# main.net
KiCad netlist of a schematic drawn in EAGLE
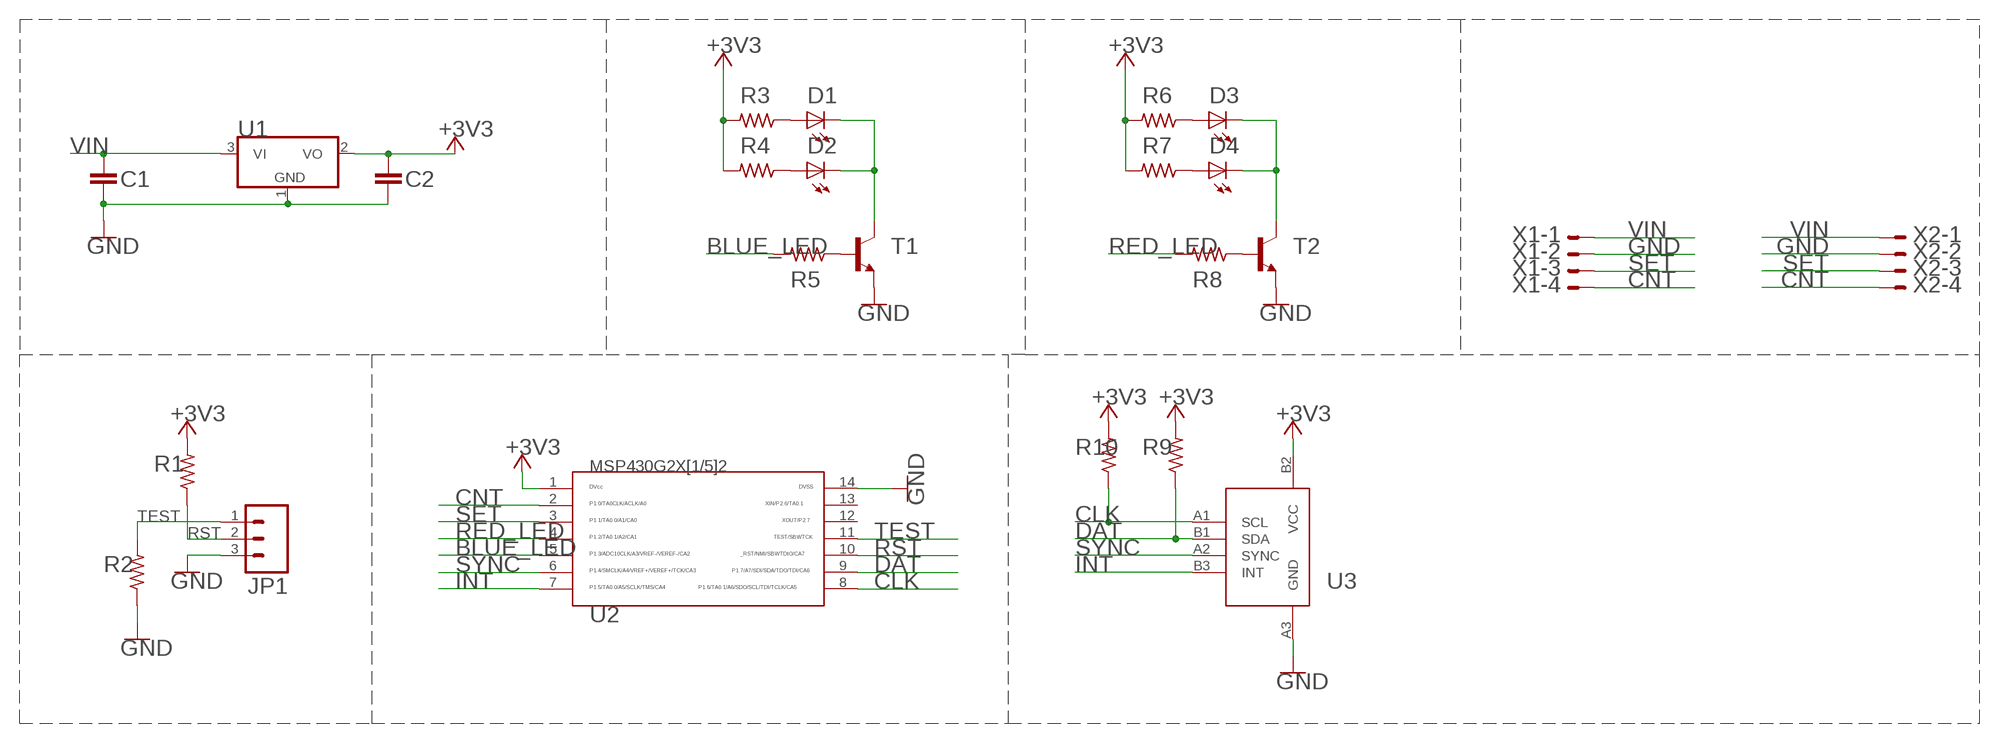
[diagram p0: schematic, sheet 1]

(export (version "E")
  (design (tool "Eeschema 10.0.6"))
  (components
    (comp (ref "C1")
      (value "C1608X5R1C106M080AB")
      (footprint "eagle-import:0603-CAP")
      (libsource (lib "eagle-import") (part "CAP0603-CAP"))
    )
    (comp (ref "C2")
      (value "C1608X5R1C106M080AB")
      (footprint "eagle-import:0603-CAP")
      (libsource (lib "eagle-import") (part "CAP0603-CAP"))
    )
    (comp (ref "D1")
      (value "VLMB1300-GS08")
      (footprint "eagle-import:LED-0603")
      (libsource (lib "eagle-import") (part "LED0603"))
    )
    (comp (ref "D2")
      (value "VLMB1300-GS08")
      (footprint "eagle-import:LED-0603")
      (libsource (lib "eagle-import") (part "LED0603"))
    )
    (comp (ref "D3")
      (value "VLMS1300-GS08")
      (footprint "eagle-import:LED-0603")
      (libsource (lib "eagle-import") (part "LED0603"))
    )
    (comp (ref "D4")
      (value "VLMS1300-GS08")
      (footprint "eagle-import:LED-0603")
      (libsource (lib "eagle-import") (part "LED0603"))
    )
    (comp (ref "JP1")
      (value "M03PTH")
      (footprint "eagle-import:1X03")
      (libsource (lib "eagle-import") (part "M03PTH"))
    )
    (comp (ref "R1")
      (value "RK73H1JTTD4702F")
      (footprint "eagle-import:R0603")
      (libsource (lib "eagle-import") (part "R-US_R0603"))
    )
    (comp (ref "R2")
      (value "RK73H1JTTD4702F")
      (footprint "eagle-import:R0603")
      (libsource (lib "eagle-import") (part "R-US_R0603"))
    )
    (comp (ref "R3")
      (value "CRCW0603200RFKEA")
      (footprint "eagle-import:R0603")
      (libsource (lib "eagle-import") (part "R-US_R0603"))
    )
    (comp (ref "R4")
      (value "CRCW0603200RFKEA")
      (footprint "eagle-import:R0603")
      (libsource (lib "eagle-import") (part "R-US_R0603"))
    )
    (comp (ref "R5")
      (value "CRCW0603200RFKEA")
      (footprint "eagle-import:R0603")
      (libsource (lib "eagle-import") (part "R-US_R0603"))
    )
    (comp (ref "R6")
      (value "CRCW0603200RFKEA")
      (footprint "eagle-import:R0603")
      (libsource (lib "eagle-import") (part "R-US_R0603"))
    )
    (comp (ref "R7")
      (value "CRCW0603200RFKEA")
      (footprint "eagle-import:R0603")
      (libsource (lib "eagle-import") (part "R-US_R0603"))
    )
    (comp (ref "R8")
      (value "CRCW0603200RFKEA")
      (footprint "eagle-import:R0603")
      (libsource (lib "eagle-import") (part "R-US_R0603"))
    )
    (comp (ref "R9")
      (value "RK73H1JTTD4701F")
      (footprint "eagle-import:R0603")
      (libsource (lib "eagle-import") (part "R-US_R0603"))
    )
    (comp (ref "R10")
      (value "RK73H1JTTD4701F")
      (footprint "eagle-import:R0603")
      (libsource (lib "eagle-import") (part "R-US_R0603"))
    )
    (comp (ref "T1")
      (value "PMBT4401,215")
      (footprint "eagle-import:SOT23-BEC")
      (libsource (lib "eagle-import") (part "-NPN-SOT23-BECMMBT4401LT1"))
    )
    (comp (ref "T2")
      (value "PMBT4401,215")
      (footprint "eagle-import:SOT23-BEC")
      (libsource (lib "eagle-import") (part "-NPN-SOT23-BECMMBT4401LT1"))
    )
    (comp (ref "U1")
      (value "MCP1703T-3002E/CB")
      (footprint "eagle-import:SOT23")
      (libsource (lib "eagle-import") (part "MCP1703CB"))
    )
    (comp (ref "U2")
      (value "MSP430G2452IPW14R")
      (footprint "eagle-import:PW14")
      (libsource (lib "eagle-import") (part "G2X[1/5]2---PW14"))
    )
    (comp (ref "U3")
      (value "TCS3414CS")
      (footprint "eagle-import:CS-6")
      (libsource (lib "eagle-import") (part "TCS3414CS"))
    )
    (comp (ref "X1")
      (value "DF13-4P-1.25V(50)")
      (footprint "eagle-import:53398-04")
      (libsource (lib "eagle-import") (part "53?-04398"))
    )
    (comp (ref "X2")
      (value "DF13-4P-1.25V(50)")
      (footprint "eagle-import:53398-04")
      (libsource (lib "eagle-import") (part "53?-04398"))
    )
  )
  (nets
    (net (code "1") (name "+3V3") (class "Default")
      (node (ref "C2") (pin "1") (pinfunction "1_1") (pintype "passive"))
      (node (ref "R1") (pin "2") (pinfunction "2_2") (pintype "passive"))
      (node (ref "R10") (pin "2") (pinfunction "2_2") (pintype "passive"))
      (node (ref "R3") (pin "2") (pinfunction "2_2") (pintype "passive"))
      (node (ref "R4") (pin "2") (pinfunction "2_2") (pintype "passive"))
      (node (ref "R6") (pin "2") (pinfunction "2_2") (pintype "passive"))
      (node (ref "R7") (pin "2") (pinfunction "2_2") (pintype "passive"))
      (node (ref "R9") (pin "2") (pinfunction "2_2") (pintype "passive"))
      (node (ref "U1") (pin "2") (pinfunction "VO_2") (pintype "passive"))
      (node (ref "U2") (pin "1") (pinfunction "1_1") (pintype "bidirectional"))
      (node (ref "U3") (pin "B2") (pinfunction "VCC_B2") (pintype "bidirectional"))
    )
    (net (code "2") (name "/BLUE_LED") (class "Default")
      (node (ref "R5") (pin "2") (pinfunction "2_2") (pintype "passive"))
      (node (ref "U2") (pin "5") (pinfunction "5_5") (pintype "bidirectional"))
    )
    (net (code "3") (name "/CLK") (class "Default")
      (node (ref "R10") (pin "1") (pinfunction "1_1") (pintype "passive"))
      (node (ref "U2") (pin "8") (pinfunction "8_8") (pintype "bidirectional"))
      (node (ref "U3") (pin "A1") (pinfunction "SCL_A1") (pintype "bidirectional"))
    )
    (net (code "4") (name "/CNT") (class "Default")
      (node (ref "U2") (pin "2") (pinfunction "2_2") (pintype "bidirectional"))
      (node (ref "X1") (pin "4") (pinfunction "S_4") (pintype "passive"))
      (node (ref "X2") (pin "4") (pinfunction "S_4") (pintype "passive"))
    )
    (net (code "5") (name "/DAT") (class "Default")
      (node (ref "R9") (pin "1") (pinfunction "1_1") (pintype "passive"))
      (node (ref "U2") (pin "9") (pinfunction "9_9") (pintype "bidirectional"))
      (node (ref "U3") (pin "B1") (pinfunction "SDA_B1") (pintype "bidirectional"))
    )
    (net (code "6") (name "/INT") (class "Default")
      (node (ref "U2") (pin "7") (pinfunction "7_7") (pintype "bidirectional"))
      (node (ref "U3") (pin "B3") (pinfunction "INT_B3") (pintype "bidirectional"))
    )
    (net (code "7") (name "/RED_LED") (class "Default")
      (node (ref "R8") (pin "2") (pinfunction "2_2") (pintype "passive"))
      (node (ref "U2") (pin "4") (pinfunction "4_4") (pintype "bidirectional"))
    )
    (net (code "8") (name "/RST") (class "Default")
      (node (ref "JP1") (pin "2") (pinfunction "2_2") (pintype "passive"))
      (node (ref "R1") (pin "1") (pinfunction "1_1") (pintype "passive"))
      (node (ref "U2") (pin "10") (pinfunction "10_10") (pintype "bidirectional"))
    )
    (net (code "9") (name "/SET") (class "Default")
      (node (ref "U2") (pin "3") (pinfunction "3_3") (pintype "bidirectional"))
      (node (ref "X1") (pin "3") (pinfunction "S_3") (pintype "passive"))
      (node (ref "X2") (pin "3") (pinfunction "S_3") (pintype "passive"))
    )
    (net (code "10") (name "/SYNC") (class "Default")
      (node (ref "U2") (pin "6") (pinfunction "6_6") (pintype "bidirectional"))
      (node (ref "U3") (pin "A2") (pinfunction "SYNC_A2") (pintype "bidirectional"))
    )
    (net (code "11") (name "/TEST") (class "Default")
      (node (ref "JP1") (pin "1") (pinfunction "1_1") (pintype "passive"))
      (node (ref "R2") (pin "2") (pinfunction "2_2") (pintype "passive"))
      (node (ref "U2") (pin "11") (pinfunction "11_11") (pintype "bidirectional"))
    )
    (net (code "12") (name "/VIN") (class "Default")
      (node (ref "C1") (pin "1") (pinfunction "1_1") (pintype "passive"))
      (node (ref "U1") (pin "3") (pinfunction "VI_3") (pintype "input"))
      (node (ref "X1") (pin "1") (pinfunction "S_1") (pintype "passive"))
      (node (ref "X2") (pin "1") (pinfunction "S_1") (pintype "passive"))
    )
    (net (code "13") (name "GND") (class "Default")
      (node (ref "C1") (pin "2") (pinfunction "2_2") (pintype "passive"))
      (node (ref "C2") (pin "2") (pinfunction "2_2") (pintype "passive"))
      (node (ref "JP1") (pin "3") (pinfunction "3_3") (pintype "passive"))
      (node (ref "R2") (pin "1") (pinfunction "1_1") (pintype "passive"))
      (node (ref "T1") (pin "E") (pinfunction "E_E") (pintype "passive"))
      (node (ref "T2") (pin "E") (pinfunction "E_E") (pintype "passive"))
      (node (ref "U1") (pin "1") (pinfunction "GND_1") (pintype "passive"))
      (node (ref "U2") (pin "14") (pinfunction "14_14") (pintype "bidirectional"))
      (node (ref "U3") (pin "A3") (pinfunction "GND_A3") (pintype "bidirectional"))
      (node (ref "X1") (pin "2") (pinfunction "S_2") (pintype "passive"))
      (node (ref "X2") (pin "2") (pinfunction "S_2") (pintype "passive"))
    )
    (net (code "14") (name "Net-(D1-PadA)") (class "Default")
      (node (ref "D1") (pin "A") (pinfunction "A_A") (pintype "passive"))
      (node (ref "R3") (pin "1") (pinfunction "1_1") (pintype "passive"))
    )
    (net (code "15") (name "Net-(D1-PadC)") (class "Default")
      (node (ref "D1") (pin "C") (pinfunction "C_C") (pintype "passive"))
      (node (ref "D2") (pin "C") (pinfunction "C_C") (pintype "passive"))
      (node (ref "T1") (pin "C") (pinfunction "C_C") (pintype "passive"))
    )
    (net (code "16") (name "Net-(D2-PadA)") (class "Default")
      (node (ref "D2") (pin "A") (pinfunction "A_A") (pintype "passive"))
      (node (ref "R4") (pin "1") (pinfunction "1_1") (pintype "passive"))
    )
    (net (code "17") (name "Net-(D3-PadA)") (class "Default")
      (node (ref "D3") (pin "A") (pinfunction "A_A") (pintype "passive"))
      (node (ref "R6") (pin "1") (pinfunction "1_1") (pintype "passive"))
    )
    (net (code "18") (name "Net-(D3-PadC)") (class "Default")
      (node (ref "D3") (pin "C") (pinfunction "C_C") (pintype "passive"))
      (node (ref "D4") (pin "C") (pinfunction "C_C") (pintype "passive"))
      (node (ref "T2") (pin "C") (pinfunction "C_C") (pintype "passive"))
    )
    (net (code "19") (name "Net-(D4-PadA)") (class "Default")
      (node (ref "D4") (pin "A") (pinfunction "A_A") (pintype "passive"))
      (node (ref "R7") (pin "1") (pinfunction "1_1") (pintype "passive"))
    )
    (net (code "20") (name "Net-(R5-Pad1)") (class "Default")
      (node (ref "R5") (pin "1") (pinfunction "1_1") (pintype "passive"))
      (node (ref "T1") (pin "B") (pinfunction "B_B") (pintype "passive"))
    )
    (net (code "21") (name "Net-(R8-Pad1)") (class "Default")
      (node (ref "R8") (pin "1") (pinfunction "1_1") (pintype "passive"))
      (node (ref "T2") (pin "B") (pinfunction "B_B") (pintype "passive"))
    )
    (net (code "22") (name "unconnected-(U2-Pad12)") (class "Default")
      (node (ref "U2") (pin "12") (pinfunction "12_12") (pintype "bidirectional"))
    )
    (net (code "23") (name "unconnected-(U2-Pad13)") (class "Default")
      (node (ref "U2") (pin "13") (pinfunction "13_13") (pintype "bidirectional"))
    )
  )
)
